# Controller.net
KiCad netlist of a schematic drawn in EAGLE
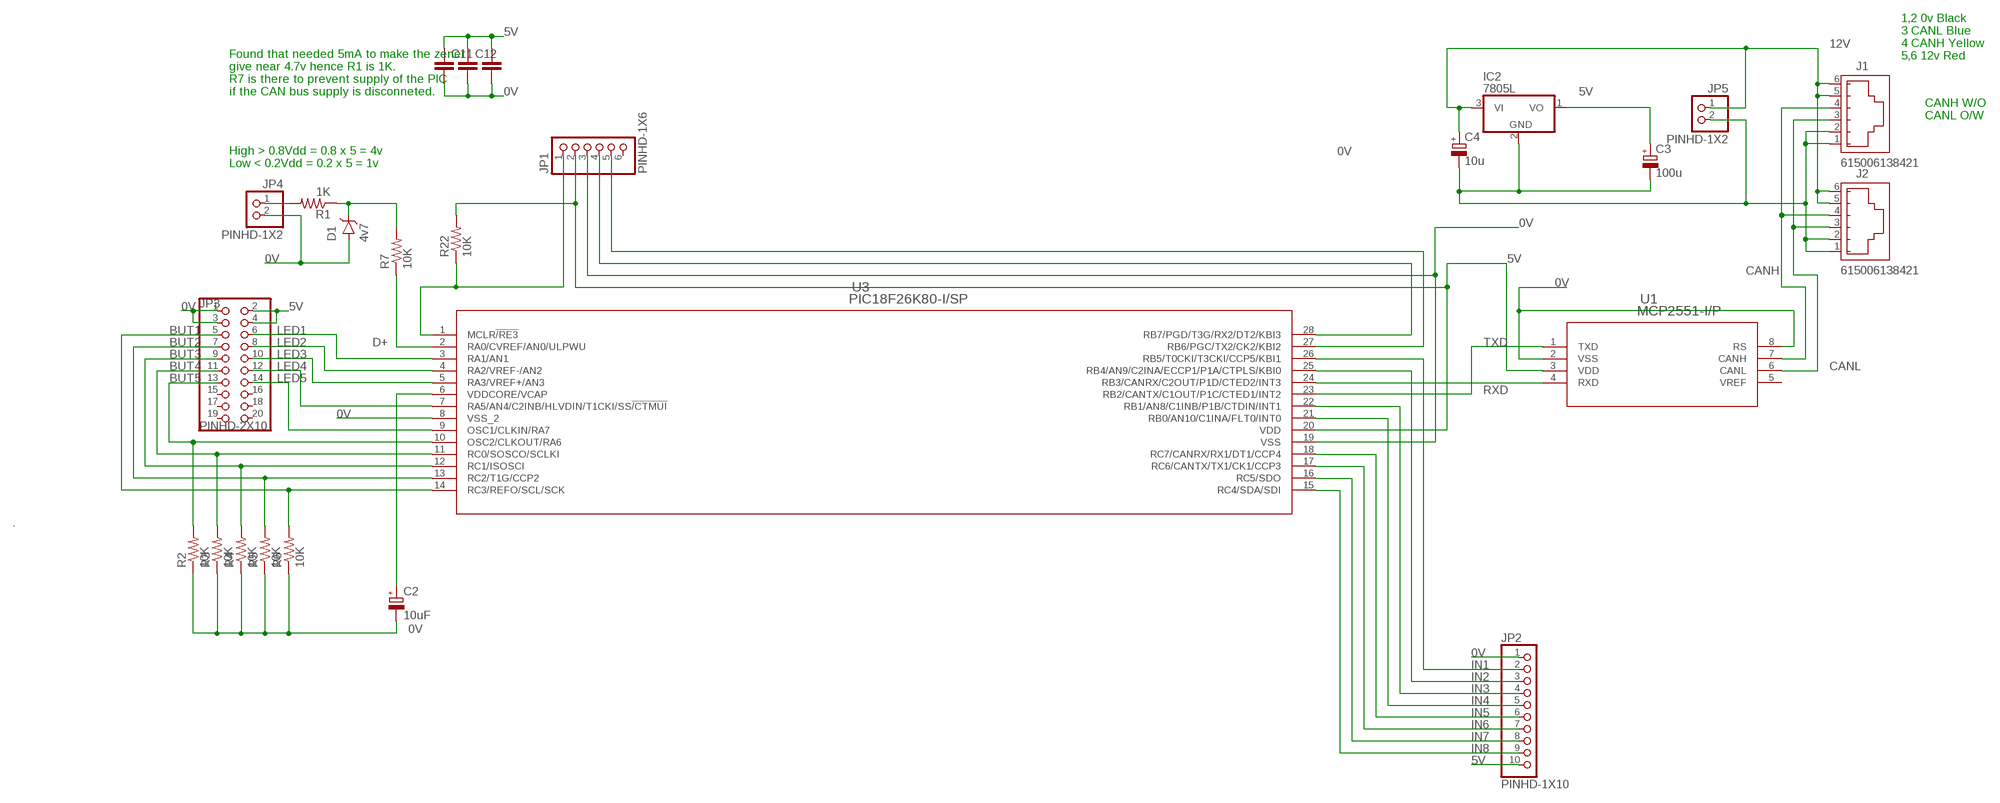
[diagram p0: schematic, sheet 1]

(export (version "E")
  (design (tool "Eeschema 10.0.6"))
  (components
    (comp (ref "C2")
      (value "10uF")
      (footprint "eagle-import:E3,5-8")
      (libsource (lib "eagle-import") (part "CPOL-EUE3.5-8"))
    )
    (comp (ref "C3")
      (value "100u")
      (footprint "eagle-import:E3,5-8")
      (libsource (lib "eagle-import") (part "CPOL-EUE3.5-8"))
    )
    (comp (ref "C4")
      (value "10u")
      (footprint "eagle-import:E3,5-8")
      (libsource (lib "eagle-import") (part "CPOL-EUE3.5-8"))
    )
    (comp (ref "C7")
      (value "C2,5-3")
      (footprint "eagle-import:C2.5-3")
      (libsource (lib "eagle-import") (part "C2,5-3"))
    )
    (comp (ref "C11")
      (value "C2,5-3")
      (footprint "eagle-import:C2.5-3")
      (libsource (lib "eagle-import") (part "C2,5-3"))
    )
    (comp (ref "C12")
      (value "C2,5-3")
      (footprint "eagle-import:C2.5-3")
      (libsource (lib "eagle-import") (part "C2,5-3"))
    )
    (comp (ref "D1")
      (value "4v7")
      (footprint "eagle-import:DO-35")
      (fields
        (field (name "DIGIKEY_PARTNO") "BZX55B15-TAPGICT-ND")
        (field (name "MANUFACTURER") "Vishay General Semiconductor - Diodes Division")
        (field (name "MPN") "BZX55B15-TAP")
        (field (name "CREATED_BY") "PCBLayout.com")
      )
      (libsource (lib "eagle-import") (part "BZX55B15-TAP"))
    )
    (comp (ref "IC2")
      (value "7805L")
      (footprint "eagle-import:TO92")
      (libsource (lib "eagle-import") (part "78L05"))
    )
    (comp (ref "J1")
      (value "615006138421")
      (footprint "eagle-import:615006138421")
      (libsource (lib "eagle-import") (part "615006138421"))
    )
    (comp (ref "J2")
      (value "615006138421")
      (footprint "eagle-import:615006138421")
      (libsource (lib "eagle-import") (part "615006138421"))
    )
    (comp (ref "JP1")
      (value "PINHD-1X6")
      (footprint "eagle-import:1X06")
      (libsource (lib "eagle-import") (part "PINHD-1X6"))
    )
    (comp (ref "JP2")
      (value "PINHD-1X10")
      (footprint "eagle-import:1X10")
      (libsource (lib "eagle-import") (part "PINHD-1X10"))
    )
    (comp (ref "JP3")
      (value "PINHD-2X10")
      (footprint "eagle-import:2X10")
      (libsource (lib "eagle-import") (part "PINHD-2X10"))
    )
    (comp (ref "JP4")
      (value "PINHD-1X2")
      (footprint "eagle-import:1X02")
      (libsource (lib "eagle-import") (part "PINHD-1X2"))
    )
    (comp (ref "JP5")
      (value "PINHD-1X2")
      (footprint "eagle-import:1X02")
      (libsource (lib "eagle-import") (part "PINHD-1X2"))
    )
    (comp (ref "R1")
      (value "1K")
      (footprint "eagle-import:0204_7")
      (libsource (lib "eagle-import") (part "RES_7"))
    )
    (comp (ref "R2")
      (value "10K")
      (footprint "eagle-import:0204_7")
      (libsource (lib "eagle-import") (part "RES_7"))
    )
    (comp (ref "R3")
      (value "10K")
      (footprint "eagle-import:0204_7")
      (libsource (lib "eagle-import") (part "RES_7"))
    )
    (comp (ref "R4")
      (value "10K")
      (footprint "eagle-import:0204_7")
      (libsource (lib "eagle-import") (part "RES_7"))
    )
    (comp (ref "R5")
      (value "10K")
      (footprint "eagle-import:0204_7")
      (libsource (lib "eagle-import") (part "RES_7"))
    )
    (comp (ref "R6")
      (value "10K")
      (footprint "eagle-import:0204_7")
      (libsource (lib "eagle-import") (part "RES_7"))
    )
    (comp (ref "R7")
      (value "10K")
      (footprint "eagle-import:0204_7")
      (libsource (lib "eagle-import") (part "RES_7"))
    )
    (comp (ref "R22")
      (value "10K")
      (footprint "eagle-import:0204_7")
      (libsource (lib "eagle-import") (part "RES_7"))
    )
    (comp (ref "U1")
      (value "MCP2551-I/P")
      (footprint "eagle-import:PDIP8_300MC_MCH")
      (fields (field (name "COPYRIGHT") "Copyright (C) 2021 Ultra Librarian. All rights reserved."))
      (libsource (lib "eagle-import") (part "MCP2551-I/P"))
    )
    (comp (ref "U3")
      (value "PIC18F26K80-I/SP")
      (footprint "eagle-import:SPDIP28_300MC_MCH")
      (fields
        (field (name "MANUFACTURER_PART_NUMBER") "pic18f26k80-i/sp")
        (field (name "COPYRIGHT") "Copyright (C) 2021 Ultra Librarian. All rights reserved.")
      )
      (libsource (lib "eagle-import") (part "PIC18F26K80-I/SP"))
    )
  )
  (nets
    (net (code "1") (name "/0V") (class "Default")
      (node (ref "C11") (pin "2") (pinfunction "2_2") (pintype "passive"))
      (node (ref "C12") (pin "2") (pinfunction "2_2") (pintype "passive"))
      (node (ref "C2") (pin "-") (pinfunction "-_-") (pintype "passive"))
      (node (ref "C3") (pin "-") (pinfunction "-_-") (pintype "passive"))
      (node (ref "C4") (pin "-") (pinfunction "-_-") (pintype "passive"))
      (node (ref "C7") (pin "2") (pinfunction "2_2") (pintype "passive"))
      (node (ref "D1") (pin "A") (pinfunction "A_A") (pintype "passive"))
      (node (ref "IC2") (pin "2") (pinfunction "GND_2") (pintype "passive"))
      (node (ref "J1") (pin "1") (pinfunction "1_1") (pintype "passive"))
      (node (ref "J1") (pin "2") (pinfunction "2_2") (pintype "passive"))
      (node (ref "J2") (pin "1") (pinfunction "1_1") (pintype "passive"))
      (node (ref "J2") (pin "2") (pinfunction "2_2") (pintype "passive"))
      (node (ref "JP1") (pin "3") (pinfunction "3_3") (pintype "passive"))
      (node (ref "JP2") (pin "1") (pinfunction "1_1") (pintype "passive"))
      (node (ref "JP3") (pin "1") (pinfunction "1_1") (pintype "passive"))
      (node (ref "JP3") (pin "3") (pinfunction "3_3") (pintype "passive"))
      (node (ref "JP4") (pin "2") (pinfunction "2_2") (pintype "passive"))
      (node (ref "JP5") (pin "2") (pinfunction "2_2") (pintype "passive"))
      (node (ref "R2") (pin "1") (pinfunction "1_1") (pintype "passive"))
      (node (ref "R3") (pin "1") (pinfunction "1_1") (pintype "passive"))
      (node (ref "R4") (pin "1") (pinfunction "1_1") (pintype "passive"))
      (node (ref "R5") (pin "1") (pinfunction "1_1") (pintype "passive"))
      (node (ref "R6") (pin "1") (pinfunction "1_1") (pintype "passive"))
      (node (ref "U1") (pin "2") (pinfunction "VSS_2") (pintype "passive"))
      (node (ref "U1") (pin "8") (pinfunction "RS_8") (pintype "passive"))
      (node (ref "U3") (pin "19") (pinfunction "VSS_19") (pintype "power_in"))
      (node (ref "U3") (pin "8") (pinfunction "VSS_2_8") (pintype "power_in"))
    )
    (net (code "2") (name "/5V") (class "Default")
      (node (ref "C11") (pin "1") (pinfunction "1_1") (pintype "passive"))
      (node (ref "C12") (pin "1") (pinfunction "1_1") (pintype "passive"))
      (node (ref "C3") (pin "+") (pinfunction "+_+") (pintype "passive"))
      (node (ref "C7") (pin "1") (pinfunction "1_1") (pintype "passive"))
      (node (ref "IC2") (pin "1") (pinfunction "VO_1") (pintype "passive"))
      (node (ref "JP1") (pin "2") (pinfunction "2_2") (pintype "passive"))
      (node (ref "JP2") (pin "10") (pinfunction "10_10") (pintype "passive"))
      (node (ref "JP3") (pin "2") (pinfunction "2_2") (pintype "passive"))
      (node (ref "JP3") (pin "4") (pinfunction "4_4") (pintype "passive"))
      (node (ref "R22") (pin "2") (pinfunction "2_2") (pintype "passive"))
      (node (ref "U1") (pin "3") (pinfunction "VDD_3") (pintype "passive"))
      (node (ref "U3") (pin "20") (pinfunction "VDD_20") (pintype "power_in"))
    )
    (net (code "3") (name "/12V") (class "Default")
      (node (ref "C4") (pin "+") (pinfunction "+_+") (pintype "passive"))
      (node (ref "IC2") (pin "3") (pinfunction "VI_3") (pintype "input"))
      (node (ref "J1") (pin "5") (pinfunction "5_5") (pintype "passive"))
      (node (ref "J1") (pin "6") (pinfunction "6_6") (pintype "passive"))
      (node (ref "J2") (pin "5") (pinfunction "5_5") (pintype "passive"))
      (node (ref "J2") (pin "6") (pinfunction "6_6") (pintype "passive"))
      (node (ref "JP5") (pin "1") (pinfunction "1_1") (pintype "passive"))
    )
    (net (code "4") (name "/BUT1") (class "Default")
      (node (ref "JP3") (pin "5") (pinfunction "5_5") (pintype "passive"))
      (node (ref "R6") (pin "2") (pinfunction "2_2") (pintype "passive"))
      (node (ref "U3") (pin "14") (pinfunction "RC3/REFO/SCL/SCK_14") (pintype "bidirectional"))
    )
    (net (code "5") (name "/BUT2") (class "Default")
      (node (ref "JP3") (pin "7") (pinfunction "7_7") (pintype "passive"))
      (node (ref "R5") (pin "2") (pinfunction "2_2") (pintype "passive"))
      (node (ref "U3") (pin "13") (pinfunction "RC2/T1G/CCP2_13") (pintype "bidirectional"))
    )
    (net (code "6") (name "/BUT3") (class "Default")
      (node (ref "JP3") (pin "9") (pinfunction "9_9") (pintype "passive"))
      (node (ref "R4") (pin "2") (pinfunction "2_2") (pintype "passive"))
      (node (ref "U3") (pin "12") (pinfunction "RC1/ISOSCI_12") (pintype "bidirectional"))
    )
    (net (code "7") (name "/BUT4") (class "Default")
      (node (ref "JP3") (pin "11") (pinfunction "11_11") (pintype "passive"))
      (node (ref "R3") (pin "2") (pinfunction "2_2") (pintype "passive"))
      (node (ref "U3") (pin "11") (pinfunction "RC0/SOSCO/SCLKI_11") (pintype "bidirectional"))
    )
    (net (code "8") (name "/BUT5") (class "Default")
      (node (ref "JP3") (pin "13") (pinfunction "13_13") (pintype "passive"))
      (node (ref "R2") (pin "2") (pinfunction "2_2") (pintype "passive"))
      (node (ref "U3") (pin "10") (pinfunction "OSC2/CLKOUT/RA6_10") (pintype "bidirectional"))
    )
    (net (code "9") (name "/CANH") (class "Default")
      (node (ref "J1") (pin "4") (pinfunction "4_4") (pintype "passive"))
      (node (ref "J2") (pin "4") (pinfunction "4_4") (pintype "passive"))
      (node (ref "U1") (pin "7") (pinfunction "CANH_7") (pintype "passive"))
    )
    (net (code "10") (name "/CANL") (class "Default")
      (node (ref "J1") (pin "3") (pinfunction "3_3") (pintype "passive"))
      (node (ref "J2") (pin "3") (pinfunction "3_3") (pintype "passive"))
      (node (ref "U1") (pin "6") (pinfunction "CANL_6") (pintype "passive"))
    )
    (net (code "11") (name "/D+") (class "Default")
      (node (ref "R7") (pin "1") (pinfunction "1_1") (pintype "passive"))
      (node (ref "U3") (pin "2") (pinfunction "RA0/CVREF/AN0/ULPWU_2") (pintype "bidirectional"))
    )
    (net (code "12") (name "/IN1") (class "Default")
      (node (ref "JP2") (pin "2") (pinfunction "2_2") (pintype "passive"))
      (node (ref "U3") (pin "26") (pinfunction "RB5/T0CKI/T3CKI/CCP5/KBI1_26") (pintype "bidirectional"))
    )
    (net (code "13") (name "/IN2") (class "Default")
      (node (ref "JP2") (pin "3") (pinfunction "3_3") (pintype "passive"))
      (node (ref "U3") (pin "25") (pinfunction "RB4/AN9/C2INA/ECCP1/P1A/CTPLS/KBI0_25") (pintype "bidirectional"))
    )
    (net (code "14") (name "/IN3") (class "Default")
      (node (ref "JP2") (pin "4") (pinfunction "4_4") (pintype "passive"))
      (node (ref "U3") (pin "22") (pinfunction "RB1/AN8/C1INB/P1B/CTDIN/INT1_22") (pintype "bidirectional"))
    )
    (net (code "15") (name "/IN4") (class "Default")
      (node (ref "JP2") (pin "5") (pinfunction "5_5") (pintype "passive"))
      (node (ref "U3") (pin "21") (pinfunction "RB0/AN10/C1INA/FLT0/INT0_21") (pintype "bidirectional"))
    )
    (net (code "16") (name "/IN5") (class "Default")
      (node (ref "JP2") (pin "6") (pinfunction "6_6") (pintype "passive"))
      (node (ref "U3") (pin "18") (pinfunction "RC7/CANRX/RX1/DT1/CCP4_18") (pintype "bidirectional"))
    )
    (net (code "17") (name "/IN6") (class "Default")
      (node (ref "JP2") (pin "7") (pinfunction "7_7") (pintype "passive"))
      (node (ref "U3") (pin "17") (pinfunction "RC6/CANTX/TX1/CK1/CCP3_17") (pintype "bidirectional"))
    )
    (net (code "18") (name "/IN7") (class "Default")
      (node (ref "JP2") (pin "8") (pinfunction "8_8") (pintype "passive"))
      (node (ref "U3") (pin "16") (pinfunction "RC5/SDO_16") (pintype "bidirectional"))
    )
    (net (code "19") (name "/IN8") (class "Default")
      (node (ref "JP2") (pin "9") (pinfunction "9_9") (pintype "passive"))
      (node (ref "U3") (pin "15") (pinfunction "RC4/SDA/SDI_15") (pintype "bidirectional"))
    )
    (net (code "20") (name "/LED1") (class "Default")
      (node (ref "JP3") (pin "6") (pinfunction "6_6") (pintype "passive"))
      (node (ref "U3") (pin "3") (pinfunction "RA1/AN1_3") (pintype "bidirectional"))
    )
    (net (code "21") (name "/LED2") (class "Default")
      (node (ref "JP3") (pin "8") (pinfunction "8_8") (pintype "passive"))
      (node (ref "U3") (pin "4") (pinfunction "RA2/VREF-/AN2_4") (pintype "bidirectional"))
    )
    (net (code "22") (name "/LED3") (class "Default")
      (node (ref "JP3") (pin "10") (pinfunction "10_10") (pintype "passive"))
      (node (ref "U3") (pin "5") (pinfunction "RA3/VREF+/AN3_5") (pintype "bidirectional"))
    )
    (net (code "23") (name "/LED4") (class "Default")
      (node (ref "JP3") (pin "12") (pinfunction "12_12") (pintype "passive"))
      (node (ref "U3") (pin "7") (pinfunction "RA5/AN4/C2INB/HLVDIN/T1CKI/SS~{/CTMUI}_7") (pintype "bidirectional"))
    )
    (net (code "24") (name "/LED5") (class "Default")
      (node (ref "JP3") (pin "14") (pinfunction "14_14") (pintype "passive"))
      (node (ref "U3") (pin "9") (pinfunction "OSC1/CLKIN/RA7_9") (pintype "bidirectional"))
    )
    (net (code "25") (name "/RXD") (class "Default")
      (node (ref "U1") (pin "4") (pinfunction "RXD_4") (pintype "passive"))
      (node (ref "U3") (pin "24") (pinfunction "RB3/CANRX/C2OUT/P1D/CTED2/INT3_24") (pintype "bidirectional"))
    )
    (net (code "26") (name "/TXD") (class "Default")
      (node (ref "U1") (pin "1") (pinfunction "TXD_1") (pintype "passive"))
      (node (ref "U3") (pin "23") (pinfunction "RB2/CANTX/C1OUT/P1C/CTED1/INT2_23") (pintype "bidirectional"))
    )
    (net (code "27") (name "Net-(D1-PadC)") (class "Default")
      (node (ref "D1") (pin "C") (pinfunction "C_C") (pintype "passive"))
      (node (ref "R1") (pin "1") (pinfunction "1_1") (pintype "passive"))
      (node (ref "R7") (pin "2") (pinfunction "2_2") (pintype "passive"))
    )
    (net (code "28") (name "Net-(JP4-Pad1)") (class "Default")
      (node (ref "JP4") (pin "1") (pinfunction "1_1") (pintype "passive"))
      (node (ref "R1") (pin "2") (pinfunction "2_2") (pintype "passive"))
    )
    (net (code "29") (name "Net-(U3-MCLR~{{slash}RE3})") (class "Default")
      (node (ref "JP1") (pin "1") (pinfunction "1_1") (pintype "passive"))
      (node (ref "R22") (pin "1") (pinfunction "1_1") (pintype "passive"))
      (node (ref "U3") (pin "1") (pinfunction "MCLR~{/RE3}_1") (pintype "bidirectional"))
    )
    (net (code "30") (name "Net-(U3-RB6{slash}PGC{slash}TX2{slash}CK2{slash}KBI2)") (class "Default")
      (node (ref "JP1") (pin "5") (pinfunction "5_5") (pintype "passive"))
      (node (ref "U3") (pin "27") (pinfunction "RB6/PGC/TX2/CK2/KBI2_27") (pintype "bidirectional"))
    )
    (net (code "31") (name "Net-(U3-RB7{slash}PGD{slash}T3G{slash}RX2{slash}DT2{slash}KBI3)") (class "Default")
      (node (ref "JP1") (pin "4") (pinfunction "4_4") (pintype "passive"))
      (node (ref "U3") (pin "28") (pinfunction "RB7/PGD/T3G/RX2/DT2/KBI3_28") (pintype "bidirectional"))
    )
    (net (code "32") (name "Net-(U3-VDDCORE{slash}VCAP)") (class "Default")
      (node (ref "C2") (pin "+") (pinfunction "+_+") (pintype "passive"))
      (node (ref "U3") (pin "6") (pinfunction "VDDCORE/VCAP_6") (pintype "power_in"))
    )
    (net (code "33") (name "unconnected-(JP1-Pad6)") (class "Default")
      (node (ref "JP1") (pin "6") (pinfunction "6_6") (pintype "passive"))
    )
    (net (code "34") (name "unconnected-(JP3-Pad15)") (class "Default")
      (node (ref "JP3") (pin "15") (pinfunction "15_15") (pintype "passive"))
    )
    (net (code "35") (name "unconnected-(JP3-Pad16)") (class "Default")
      (node (ref "JP3") (pin "16") (pinfunction "16_16") (pintype "passive"))
    )
    (net (code "36") (name "unconnected-(JP3-Pad17)") (class "Default")
      (node (ref "JP3") (pin "17") (pinfunction "17_17") (pintype "passive"))
    )
    (net (code "37") (name "unconnected-(JP3-Pad18)") (class "Default")
      (node (ref "JP3") (pin "18") (pinfunction "18_18") (pintype "passive"))
    )
    (net (code "38") (name "unconnected-(JP3-Pad19)") (class "Default")
      (node (ref "JP3") (pin "19") (pinfunction "19_19") (pintype "passive"))
    )
    (net (code "39") (name "unconnected-(JP3-Pad20)") (class "Default")
      (node (ref "JP3") (pin "20") (pinfunction "20_20") (pintype "passive"))
    )
    (net (code "40") (name "unconnected-(U1-VREF-Pad5)") (class "Default")
      (node (ref "U1") (pin "5") (pinfunction "VREF_5") (pintype "passive"))
    )
  )
)
